# CPU.net
KiCad netlist of a schematic drawn in Altium Designer
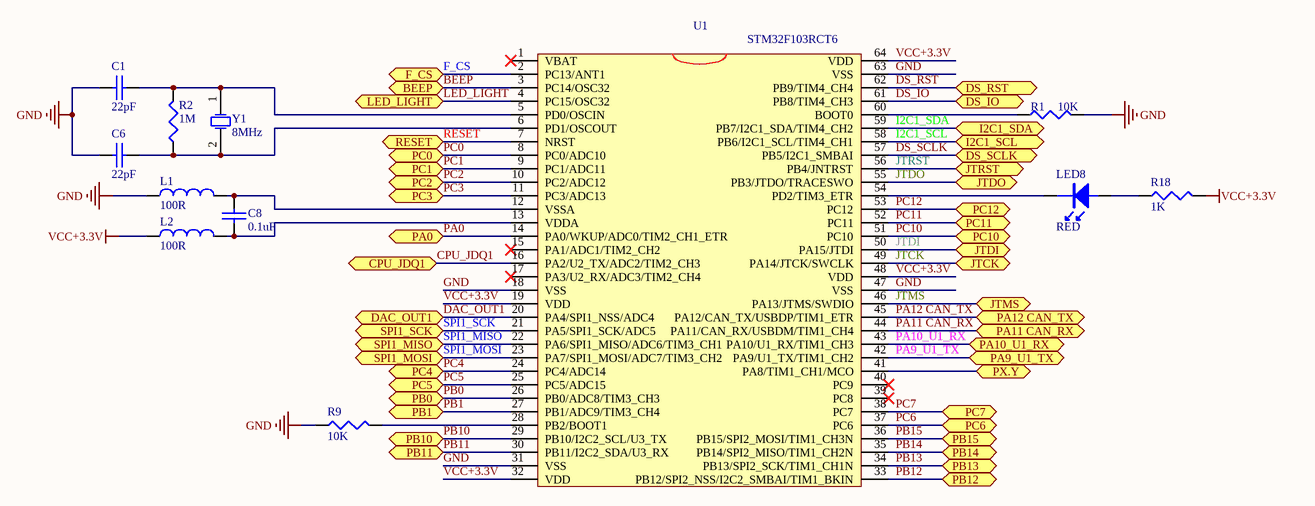
[diagram p0: CPU.SchDoc]

(export (version "E")
  (design (tool "Eeschema 10.0.6"))
  (components
    (comp (ref "C1")
      (value "22pF")
      (footprint "0603")
      (description "0603陶瓷贴片电容")
      (libsource (lib "INSPUR_PCB") (part "CAP-0603"))
    )
    (comp (ref "C6")
      (value "22pF")
      (footprint "0603")
      (description "0603陶瓷贴片电容")
      (libsource (lib "INSPUR_PCB") (part "CAP-0603"))
    )
    (comp (ref "C8")
      (value "0.1uF")
      (footprint "0603")
      (description "0603陶瓷贴片电容")
      (libsource (lib "INSPUR_PCB") (part "CAP-0603"))
    )
    (comp (ref "L1") (value "100R") (footprint "0805") (libsource (lib "INSPUR_SCH") (part "INDUCTOR")))
    (comp (ref "L2") (value "100R") (footprint "0805") (libsource (lib "INSPUR_SCH") (part "INDUCTOR")))
    (comp (ref "LED8")
      (value "RED")
      (footprint "LED-0603")
      (description "LED贴片发光二极管0603封装")
      (libsource (lib "INSPUR_PCB") (part "LED-0603"))
    )
    (comp (ref "R1")
      (value "10K")
      (footprint "0603")
      (description "陶瓷贴片电阻0603封装")
      (libsource (lib "INSPUR_PCB") (part "RES-0603"))
    )
    (comp (ref "R2")
      (value "1M")
      (footprint "0603")
      (description "陶瓷贴片电阻0603封装")
      (libsource (lib "INSPUR_PCB") (part "RES-0603"))
    )
    (comp (ref "R9")
      (value "10K")
      (footprint "0603")
      (description "陶瓷贴片电阻0603封装")
      (libsource (lib "INSPUR_PCB") (part "RES-0603"))
    )
    (comp (ref "R18")
      (value "1K")
      (footprint "0603")
      (description "陶瓷贴片电阻0603封装")
      (libsource (lib "INSPUR_PCB") (part "RES-0603"))
    )
    (comp (ref "U1")
      (value "STM32F103RCT6")
      (footprint "mylib:LQFP64_N")
      (description "STM32F103RCT6   LQFP64封装")
      (libsource (lib "mylib") (part "STM32F103RBT6"))
    )
    (comp (ref "Y1")
      (value "8MHz")
      (footprint "XTAL_US")
      (description "Crystal Oscillator")
      (fields (field (name "PUBLISHER") "Altium Limited"))
      (libsource (lib "mylib") (part "XTAL"))
    )
  )
  (nets
    (net (code "1") (name "/BEEP") (class "Default")
      (node (ref "U1") (pin "3") (pinfunction "PC14/OSC32_3") (pintype "passive"))
    )
    (net (code "2") (name "/CPU_JDQ1") (class "Default")
      (node (ref "U1") (pin "16") (pinfunction "PA2/U2_TX/ADC2/TIM2_CH3_16") (pintype "passive"))
    )
    (net (code "3") (name "/DAC_OUT1") (class "Default")
      (node (ref "U1") (pin "20") (pinfunction "PA4/SPI1_NSS/ADC4_20") (pintype "passive"))
    )
    (net (code "4") (name "/DS_IO") (class "Default")
      (node (ref "U1") (pin "61") (pinfunction "PB8/TIM4_CH3_61") (pintype "passive"))
    )
    (net (code "5") (name "/DS_RST") (class "Default")
      (node (ref "U1") (pin "62") (pinfunction "PB9/TIM4_CH4_62") (pintype "passive"))
    )
    (net (code "6") (name "/DS_SCLK") (class "Default")
      (node (ref "U1") (pin "57") (pinfunction "PB5/I2C1_SMBAI_57") (pintype "passive"))
    )
    (net (code "7") (name "/F_CS") (class "Default")
      (node (ref "U1") (pin "2") (pinfunction "PC13/ANT1_2") (pintype "passive"))
    )
    (net (code "8") (name "/I2C1_SCL") (class "Default")
      (node (ref "U1") (pin "58") (pinfunction "PB6/I2C1_SCL/TIM4_CH1_58") (pintype "passive"))
    )
    (net (code "9") (name "/I2C1_SDA") (class "Default")
      (node (ref "U1") (pin "59") (pinfunction "PB7/I2C1_SDA/TIM4_CH2_59") (pintype "passive"))
    )
    (net (code "10") (name "/JTCK") (class "Default")
      (node (ref "U1") (pin "49") (pinfunction "PA14/JTCK/SWCLK_49") (pintype "passive"))
    )
    (net (code "11") (name "/JTDI") (class "Default")
      (node (ref "U1") (pin "50") (pinfunction "PA15/JTDI_50") (pintype "passive"))
    )
    (net (code "12") (name "/JTDO") (class "Default")
      (node (ref "U1") (pin "55") (pinfunction "PB3/JTDO/TRACESWO_55") (pintype "passive"))
    )
    (net (code "13") (name "/JTMS") (class "Default")
      (node (ref "U1") (pin "46") (pinfunction "PA13/JTMS/SWDIO_46") (pintype "passive"))
    )
    (net (code "14") (name "/JTRST") (class "Default")
      (node (ref "U1") (pin "56") (pinfunction "PB4/JNTRST_56") (pintype "passive"))
    )
    (net (code "15") (name "/LED_LIGHT") (class "Default")
      (node (ref "U1") (pin "4") (pinfunction "PC15/OSC32_4") (pintype "passive"))
    )
    (net (code "16") (name "/PA0") (class "Default")
      (node (ref "U1") (pin "14") (pinfunction "PA0/WKUP/ADC0/TIM2_CH1_ETR_14") (pintype "passive"))
    )
    (net (code "17") (name "/PA9_U1_TX") (class "Default")
      (node (ref "U1") (pin "42") (pinfunction "PA9/U1_TX/TIM1_CH2_42") (pintype "passive"))
    )
    (net (code "18") (name "/PA10_U1_RX") (class "Default")
      (node (ref "U1") (pin "43") (pinfunction "PA10/U1_RX/TIM1_CH3_43") (pintype "passive"))
    )
    (net (code "19") (name "/PA11 CAN_RX") (class "Default")
      (node (ref "U1") (pin "44") (pinfunction "PA11/CAN_RX/USBDM/TIM1_CH4_44") (pintype "passive"))
    )
    (net (code "20") (name "/PA12 CAN_TX") (class "Default")
      (node (ref "U1") (pin "45") (pinfunction "PA12/CAN_TX/USBDP/TIM1_ETR_45") (pintype "passive"))
    )
    (net (code "21") (name "/PB0") (class "Default")
      (node (ref "U1") (pin "26") (pinfunction "PB0/ADC8/TIM3_CH3_26") (pintype "passive"))
    )
    (net (code "22") (name "/PB1") (class "Default")
      (node (ref "U1") (pin "27") (pinfunction "PB1/ADC9/TIM3_CH4_27") (pintype "passive"))
    )
    (net (code "23") (name "/PB10") (class "Default")
      (node (ref "U1") (pin "29") (pinfunction "PB10/I2C2_SCL/U3_TX_29") (pintype "passive"))
    )
    (net (code "24") (name "/PB11") (class "Default")
      (node (ref "U1") (pin "30") (pinfunction "PB11/I2C2_SDA/U3_RX_30") (pintype "passive"))
    )
    (net (code "25") (name "/PB12") (class "Default")
      (node (ref "U1") (pin "33") (pinfunction "PB12/SPI2_NSS/I2C2_SMBAI/TIM1_BKIN_33") (pintype "passive"))
    )
    (net (code "26") (name "/PB13") (class "Default")
      (node (ref "U1") (pin "34") (pinfunction "PB13/SPI2_SCK/TIM1_CH1N_34") (pintype "passive"))
    )
    (net (code "27") (name "/PB14") (class "Default")
      (node (ref "U1") (pin "35") (pinfunction "PB14/SPI2_MISO/TIM1_CH2N_35") (pintype "passive"))
    )
    (net (code "28") (name "/PB15") (class "Default")
      (node (ref "U1") (pin "36") (pinfunction "PB15/SPI2_MOSI/TIM1_CH3N_36") (pintype "passive"))
    )
    (net (code "29") (name "/PC0") (class "Default")
      (node (ref "U1") (pin "8") (pinfunction "PC0/ADC10_8") (pintype "passive"))
    )
    (net (code "30") (name "/PC1") (class "Default")
      (node (ref "U1") (pin "9") (pinfunction "PC1/ADC11_9") (pintype "passive"))
    )
    (net (code "31") (name "/PC2") (class "Default")
      (node (ref "U1") (pin "10") (pinfunction "PC2/ADC12_10") (pintype "passive"))
    )
    (net (code "32") (name "/PC3") (class "Default")
      (node (ref "U1") (pin "11") (pinfunction "PC3/ADC13_11") (pintype "passive"))
    )
    (net (code "33") (name "/PC4") (class "Default")
      (node (ref "U1") (pin "24") (pinfunction "PC4/ADC14_24") (pintype "passive"))
    )
    (net (code "34") (name "/PC5") (class "Default")
      (node (ref "U1") (pin "25") (pinfunction "PC5/ADC15_25") (pintype "passive"))
    )
    (net (code "35") (name "/PC6") (class "Default")
      (node (ref "U1") (pin "37") (pinfunction "PC6_37") (pintype "passive"))
    )
    (net (code "36") (name "/PC7") (class "Default")
      (node (ref "U1") (pin "38") (pinfunction "PC7_38") (pintype "passive"))
    )
    (net (code "37") (name "/PC10") (class "Default")
      (node (ref "U1") (pin "51") (pinfunction "PC10_51") (pintype "passive"))
    )
    (net (code "38") (name "/PC11") (class "Default")
      (node (ref "U1") (pin "52") (pinfunction "PC11_52") (pintype "passive"))
    )
    (net (code "39") (name "/PC12") (class "Default")
      (node (ref "U1") (pin "53") (pinfunction "PC12_53") (pintype "passive"))
    )
    (net (code "40") (name "/PX.Y") (class "Default")
      (node (ref "U1") (pin "41") (pinfunction "PA8/TIM1_CH1/MCO_41") (pintype "passive"))
    )
    (net (code "41") (name "/RESET") (class "Default")
      (node (ref "U1") (pin "7") (pinfunction "NRST_7") (pintype "passive"))
    )
    (net (code "42") (name "/SPI1_MISO") (class "Default")
      (node (ref "U1") (pin "22") (pinfunction "PA6/SPI1_MISO/ADC6/TIM3_CH1_22") (pintype "passive"))
    )
    (net (code "43") (name "/SPI1_MOSI") (class "Default")
      (node (ref "U1") (pin "23") (pinfunction "PA7/SPI1_MOSI/ADC7/TIM3_CH2_23") (pintype "passive"))
    )
    (net (code "44") (name "/SPI1_SCK") (class "Default")
      (node (ref "U1") (pin "21") (pinfunction "PA5/SPI1_SCK/ADC5_21") (pintype "passive"))
    )
    (net (code "45") (name "GND") (class "Default")
      (node (ref "C1") (pin "1") (pinfunction "1_1") (pintype "passive"))
      (node (ref "C6") (pin "1") (pinfunction "1_1") (pintype "passive"))
      (node (ref "L1") (pin "1") (pinfunction "1_1") (pintype "passive"))
      (node (ref "R1") (pin "2") (pinfunction "2_2") (pintype "passive"))
      (node (ref "R9") (pin "1") (pinfunction "1_1") (pintype "passive"))
      (node (ref "U1") (pin "18") (pinfunction "VSS_18") (pintype "passive"))
      (node (ref "U1") (pin "31") (pinfunction "VSS_31") (pintype "passive"))
      (node (ref "U1") (pin "47") (pinfunction "VSS_47") (pintype "passive"))
      (node (ref "U1") (pin "63") (pinfunction "VSS_63") (pintype "passive"))
    )
    (net (code "46") (name "Net-(LED8-Pad1)") (class "Default")
      (node (ref "LED8") (pin "1") (pinfunction "1_1") (pintype "passive"))
      (node (ref "R18") (pin "1") (pinfunction "1_1") (pintype "passive"))
    )
    (net (code "47") (name "Net-(U1-BOOT0)") (class "Default")
      (node (ref "R1") (pin "1") (pinfunction "1_1") (pintype "passive"))
      (node (ref "U1") (pin "60") (pinfunction "BOOT0_60") (pintype "passive"))
    )
    (net (code "48") (name "Net-(U1-PB2{slash}BOOT1)") (class "Default")
      (node (ref "R9") (pin "2") (pinfunction "2_2") (pintype "passive"))
      (node (ref "U1") (pin "28") (pinfunction "PB2/BOOT1_28") (pintype "passive"))
    )
    (net (code "49") (name "Net-(U1-PD0{slash}OSCIN)") (class "Default")
      (node (ref "C1") (pin "2") (pinfunction "2_2") (pintype "passive"))
      (node (ref "R2") (pin "2") (pinfunction "2_2") (pintype "passive"))
      (node (ref "U1") (pin "5") (pinfunction "PD0/OSCIN_5") (pintype "passive"))
      (node (ref "Y1") (pin "1") (pinfunction "OSC1_1") (pintype "passive"))
    )
    (net (code "50") (name "Net-(U1-PD1{slash}OSCOUT)") (class "Default")
      (node (ref "C6") (pin "2") (pinfunction "2_2") (pintype "passive"))
      (node (ref "R2") (pin "1") (pinfunction "1_1") (pintype "passive"))
      (node (ref "U1") (pin "6") (pinfunction "PD1/OSCOUT_6") (pintype "passive"))
      (node (ref "Y1") (pin "2") (pinfunction "OSC2_2") (pintype "passive"))
    )
    (net (code "51") (name "Net-(U1-PD2{slash}TIM3_ETR)") (class "Default")
      (node (ref "LED8") (pin "2") (pinfunction "2_2") (pintype "passive"))
      (node (ref "U1") (pin "54") (pinfunction "PD2/TIM3_ETR_54") (pintype "passive"))
    )
    (net (code "52") (name "Net-(U1-VDDA)") (class "Default")
      (node (ref "C8") (pin "1") (pinfunction "1_1") (pintype "passive"))
      (node (ref "L2") (pin "2") (pinfunction "2_2") (pintype "passive"))
      (node (ref "U1") (pin "13") (pinfunction "VDDA_13") (pintype "passive"))
    )
    (net (code "53") (name "Net-(U1-VSSA)") (class "Default")
      (node (ref "C8") (pin "2") (pinfunction "2_2") (pintype "passive"))
      (node (ref "L1") (pin "2") (pinfunction "2_2") (pintype "passive"))
      (node (ref "U1") (pin "12") (pinfunction "VSSA_12") (pintype "passive"))
    )
    (net (code "54") (name "VCC+3.3V") (class "Default")
      (node (ref "L2") (pin "1") (pinfunction "1_1") (pintype "passive"))
      (node (ref "R18") (pin "2") (pinfunction "2_2") (pintype "passive"))
      (node (ref "U1") (pin "19") (pinfunction "VDD_19") (pintype "passive"))
      (node (ref "U1") (pin "32") (pinfunction "VDD_32") (pintype "passive"))
      (node (ref "U1") (pin "48") (pinfunction "VDD_48") (pintype "passive"))
      (node (ref "U1") (pin "64") (pinfunction "VDD_64") (pintype "passive"))
    )
    (net (code "55") (name "unconnected-(U1-PA1{slash}ADC1{slash}TIM2_CH2-Pad15)") (class "Default")
      (node (ref "U1") (pin "15") (pinfunction "PA1/ADC1/TIM2_CH2_15") (pintype "passive+no_connect"))
    )
    (net (code "56") (name "unconnected-(U1-PA3{slash}U2_RX{slash}ADC3{slash}TIM2_CH4-Pad17)") (class "Default")
      (node (ref "U1") (pin "17") (pinfunction "PA3/U2_RX/ADC3/TIM2_CH4_17") (pintype "passive+no_connect"))
    )
    (net (code "57") (name "unconnected-(U1-PC8-Pad39)") (class "Default")
      (node (ref "U1") (pin "39") (pinfunction "PC8_39") (pintype "passive+no_connect"))
    )
    (net (code "58") (name "unconnected-(U1-PC9-Pad40)") (class "Default")
      (node (ref "U1") (pin "40") (pinfunction "PC9_40") (pintype "passive+no_connect"))
    )
    (net (code "59") (name "unconnected-(U1-VBAT-Pad1)") (class "Default")
      (node (ref "U1") (pin "1") (pinfunction "VBAT_1") (pintype "passive+no_connect"))
    )
  )
)
